# usb_uart.net
KiCad netlist of a schematic drawn in Altium Designer
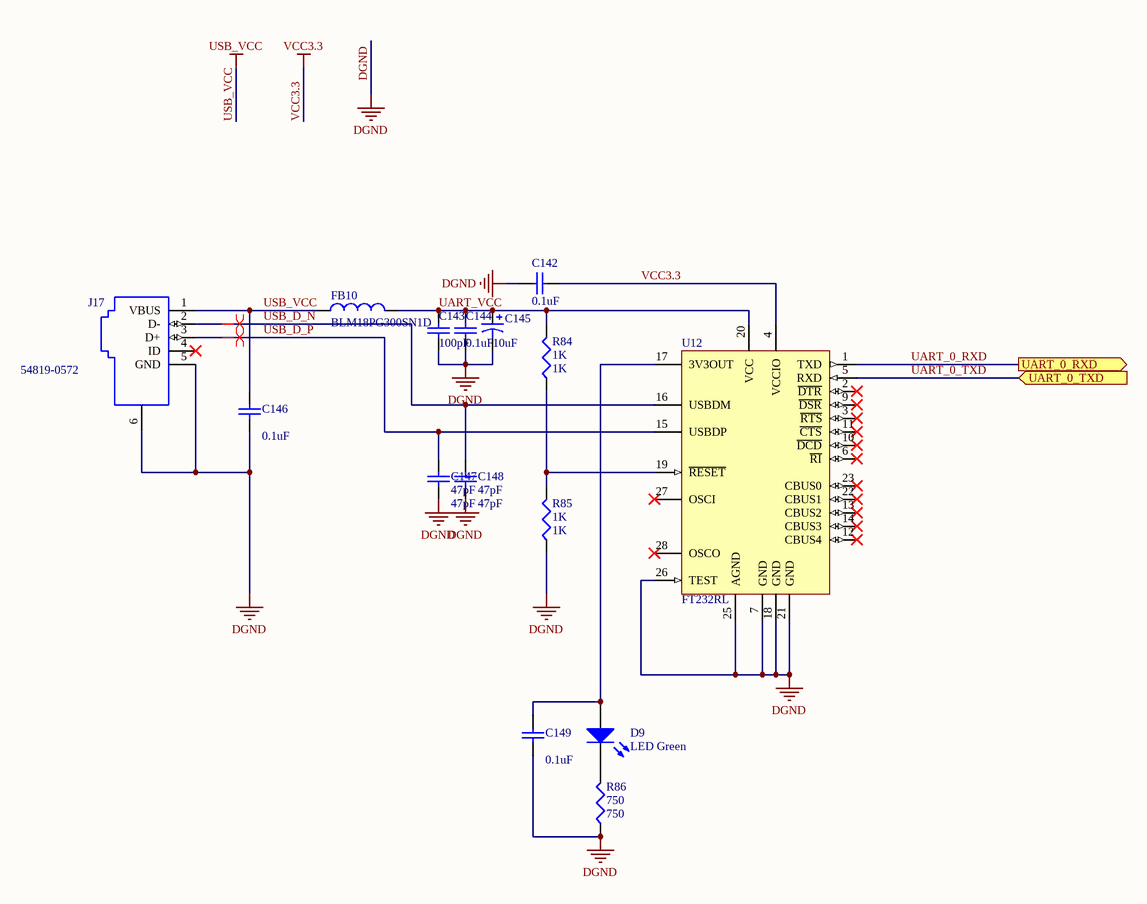
[diagram p0: usb_uart.SchDoc]

(export (version "E")
  (design (tool "Eeschema 10.0.6"))
  (components
    (comp (ref "C142")
      (value "0.1uF")
      (footprint "0402")
      (description "Capacitor (Semiconductor SIM Model)")
      (fields (field (name "PUBLISHER") "Altium Limited"))
      (libsource (lib "Miscellaneous Devices") (part "Cap Semi"))
    )
    (comp (ref "C143")
      (value "100pF")
      (footprint "0402")
      (description "Capacitor (Semiconductor SIM Model)")
      (fields (field (name "PUBLISHER") "Altium Limited"))
      (libsource (lib "Miscellaneous Devices") (part "Cap Semi"))
    )
    (comp (ref "C144")
      (value "0.1uF")
      (footprint "0402")
      (description "Capacitor (Semiconductor SIM Model)")
      (fields (field (name "PUBLISHER") "Altium Limited"))
      (libsource (lib "Miscellaneous Devices") (part "Cap Semi"))
    )
    (comp (ref "C145")
      (value "10uF")
      (footprint "C0805")
      (description "Polarized Capacitor (Surface Mount)")
      (fields (field (name "PUBLISHER") "Altium Limited"))
      (libsource (lib "Miscellaneous Devices") (part "Cap Pol3"))
    )
    (comp (ref "C146")
      (value "0.1uF")
      (footprint "0402")
      (description "Capacitor (Semiconductor SIM Model)")
      (fields (field (name "PUBLISHER") "Altium Limited"))
      (libsource (lib "Miscellaneous Devices") (part "Cap Semi"))
    )
    (comp (ref "C147")
      (value "47pF")
      (footprint "0402")
      (description "Capacitor (Semiconductor SIM Model)")
      (fields (field (name "ALTIUM_VALUE") "47pF") (field (name "PUBLISHER") "Altium Limited"))
      (libsource (lib "Miscellaneous Devices") (part "Cap Semi"))
    )
    (comp (ref "C148")
      (value "47pF")
      (footprint "0402")
      (description "Capacitor (Semiconductor SIM Model)")
      (fields (field (name "ALTIUM_VALUE") "47pF") (field (name "PUBLISHER") "Altium Limited"))
      (libsource (lib "Miscellaneous Devices") (part "Cap Semi"))
    )
    (comp (ref "C149")
      (value "0.1uF")
      (footprint "0402")
      (description "Capacitor (Semiconductor SIM Model)")
      (fields (field (name "PUBLISHER") "Altium Limited"))
      (libsource (lib "Miscellaneous Devices") (part "Cap Semi"))
    )
    (comp (ref "D9")
      (value "LED Green")
      (footprint "1608[0603]")
      (description "Typical RED, GREEN, YELLOW, AMBER GaAs LED")
      (fields (field (name "PUBLISHER") "Altium Limited"))
      (libsource (lib "Miscellaneous Devices") (part "LED2"))
    )
    (comp (ref "FB10")
      (value "BLM18PG300SN1D")
      (footprint "1608[0603]")
      (description "FERRITE CHIP 30 OHM 1000MA 0603")
      (libsource (lib "SDR") (part "Ferrite Bead"))
    )
    (comp (ref "J17")
      (value "54819-0572")
      (footprint "Mini USB")
      (description "CONN RECEPT MINIUSB R/A 5POS SMD")
      (libsource (lib "SDR") (part "Mini USB"))
    )
    (comp (ref "R84")
      (value "1K")
      (footprint "0402")
      (description "Resistor")
      (fields (field (name "ALTIUM_VALUE") "1K") (field (name "PUBLISHER") "Altium Limited"))
      (libsource (lib "Miscellaneous Devices") (part "Res3"))
    )
    (comp (ref "R85")
      (value "1K")
      (footprint "0402")
      (description "Resistor")
      (fields (field (name "ALTIUM_VALUE") "1K") (field (name "PUBLISHER") "Altium Limited"))
      (libsource (lib "Miscellaneous Devices") (part "Res3"))
    )
    (comp (ref "R86")
      (value "750")
      (footprint "0402")
      (description "Resistor")
      (fields (field (name "ALTIUM_VALUE") "750") (field (name "PUBLISHER") "Altium Limited"))
      (libsource (lib "Miscellaneous Devices") (part "Res3"))
    )
    (comp (ref "U12")
      (value "FT232RL")
      (footprint "FTDI Footprints:SSOP65P780X200-28N")
      (description "USB to UART interface in SSOP-28 package")
      (fields
        (field (name "MANUFACTURER") "Future Technology Devices International Ltd. (FTDI)")
        (field (name "DIGIKEYPARTNO") "768-1007-1-ND")
        (field (name "PUBLISHER") "FTDI Ltd.")
      )
      (libsource (lib "FTDI Symbols") (part "FT232RL"))
    )
  )
  (nets
    (net (code "1") (name "/UART_0_RXD") (class "Default")
      (node (ref "U12") (pin "1") (pinfunction "TXD_1") (pintype "output"))
    )
    (net (code "2") (name "/UART_0_TXD") (class "Default")
      (node (ref "U12") (pin "5") (pinfunction "RXD_5") (pintype "input"))
    )
    (net (code "3") (name "/UART_VCC") (class "Default")
      (node (ref "C143") (pin "2") (pinfunction "2_2") (pintype "passive"))
      (node (ref "C144") (pin "2") (pinfunction "2_2") (pintype "passive"))
      (node (ref "C145") (pin "1") (pinfunction "1_1") (pintype "passive"))
      (node (ref "FB10") (pin "2") (pinfunction "2_2") (pintype "passive"))
      (node (ref "R84") (pin "2") (pinfunction "2_2") (pintype "passive"))
      (node (ref "U12") (pin "20") (pinfunction "VCC_20") (pintype "power_in"))
    )
    (net (code "4") (name "/USB_D_N") (class "Default")
      (node (ref "C148") (pin "2") (pinfunction "2_2") (pintype "passive"))
      (node (ref "J17") (pin "2") (pinfunction "D-_2") (pintype "bidirectional"))
      (node (ref "U12") (pin "16") (pinfunction "USBDM_16") (pintype "passive"))
    )
    (net (code "5") (name "/USB_D_P") (class "Default")
      (node (ref "C147") (pin "2") (pinfunction "2_2") (pintype "passive"))
      (node (ref "J17") (pin "3") (pinfunction "D+_3") (pintype "bidirectional"))
      (node (ref "U12") (pin "15") (pinfunction "USBDP_15") (pintype "passive"))
    )
    (net (code "6") (name "DGND") (class "Default")
      (node (ref "C142") (pin "1") (pinfunction "1_1") (pintype "passive"))
      (node (ref "C143") (pin "1") (pinfunction "1_1") (pintype "passive"))
      (node (ref "C144") (pin "1") (pinfunction "1_1") (pintype "passive"))
      (node (ref "C145") (pin "2") (pinfunction "2_2") (pintype "passive"))
      (node (ref "C146") (pin "1") (pinfunction "1_1") (pintype "passive"))
      (node (ref "C147") (pin "1") (pinfunction "1_1") (pintype "passive"))
      (node (ref "C148") (pin "1") (pinfunction "1_1") (pintype "passive"))
      (node (ref "C149") (pin "1") (pinfunction "1_1") (pintype "passive"))
      (node (ref "J17") (pin "5") (pinfunction "GND_5") (pintype "power_in"))
      (node (ref "J17") (pin "6") (pinfunction "SHIELD_6") (pintype "passive"))
      (node (ref "R85") (pin "1") (pinfunction "1_1") (pintype "passive"))
      (node (ref "R86") (pin "1") (pinfunction "1_1") (pintype "passive"))
      (node (ref "U12") (pin "18") (pinfunction "GND_18") (pintype "power_in"))
      (node (ref "U12") (pin "21") (pinfunction "GND_21") (pintype "power_in"))
      (node (ref "U12") (pin "25") (pinfunction "AGND_25") (pintype "power_in"))
      (node (ref "U12") (pin "26") (pinfunction "TEST_26") (pintype "input"))
      (node (ref "U12") (pin "7") (pinfunction "GND_7") (pintype "power_in"))
    )
    (net (code "7") (name "Net-(D9-A)") (class "Default")
      (node (ref "C149") (pin "2") (pinfunction "2_2") (pintype "passive"))
      (node (ref "D9") (pin "1") (pinfunction "A_1") (pintype "passive"))
      (node (ref "U12") (pin "17") (pinfunction "3V3OUT_17") (pintype "power_in"))
    )
    (net (code "8") (name "Net-(D9-K)") (class "Default")
      (node (ref "D9") (pin "2") (pinfunction "K_2") (pintype "passive"))
      (node (ref "R86") (pin "2") (pinfunction "2_2") (pintype "passive"))
    )
    (net (code "9") (name "Net-(U12-~{RESET})") (class "Default")
      (node (ref "R84") (pin "1") (pinfunction "1_1") (pintype "passive"))
      (node (ref "R85") (pin "2") (pinfunction "2_2") (pintype "passive"))
      (node (ref "U12") (pin "19") (pinfunction "~{RESET}_19") (pintype "input"))
    )
    (net (code "10") (name "USB_VCC") (class "Default")
      (node (ref "C146") (pin "2") (pinfunction "2_2") (pintype "passive"))
      (node (ref "FB10") (pin "1") (pinfunction "1_1") (pintype "passive"))
      (node (ref "J17") (pin "1") (pinfunction "VBUS_1") (pintype "power_in"))
    )
    (net (code "11") (name "VCC3.3") (class "Default")
      (node (ref "C142") (pin "2") (pinfunction "2_2") (pintype "passive"))
      (node (ref "U12") (pin "4") (pinfunction "VCCIO_4") (pintype "power_in"))
    )
    (net (code "12") (name "unconnected-(J17-ID-Pad4)") (class "Default")
      (node (ref "J17") (pin "4") (pinfunction "ID_4") (pintype "passive+no_connect"))
    )
    (net (code "13") (name "unconnected-(U12-CBUS0-Pad23)") (class "Default")
      (node (ref "U12") (pin "23") (pinfunction "CBUS0_23") (pintype "bidirectional+no_connect"))
    )
    (net (code "14") (name "unconnected-(U12-CBUS1-Pad22)") (class "Default")
      (node (ref "U12") (pin "22") (pinfunction "CBUS1_22") (pintype "bidirectional+no_connect"))
    )
    (net (code "15") (name "unconnected-(U12-CBUS2-Pad13)") (class "Default")
      (node (ref "U12") (pin "13") (pinfunction "CBUS2_13") (pintype "bidirectional+no_connect"))
    )
    (net (code "16") (name "unconnected-(U12-CBUS3-Pad14)") (class "Default")
      (node (ref "U12") (pin "14") (pinfunction "CBUS3_14") (pintype "bidirectional+no_connect"))
    )
    (net (code "17") (name "unconnected-(U12-CBUS4-Pad12)") (class "Default")
      (node (ref "U12") (pin "12") (pinfunction "CBUS4_12") (pintype "bidirectional+no_connect"))
    )
    (net (code "18") (name "unconnected-(U12-NC-Pad8)") (class "Default")
      (node (ref "U12") (pin "8") (pinfunction "NC_8") (pintype "passive"))
    )
    (net (code "19") (name "unconnected-(U12-NC-Pad24)") (class "Default")
      (node (ref "U12") (pin "24") (pinfunction "NC_24") (pintype "passive"))
    )
    (net (code "20") (name "unconnected-(U12-OSCI-Pad27)") (class "Default")
      (node (ref "U12") (pin "27") (pinfunction "OSCI_27") (pintype "passive+no_connect"))
    )
    (net (code "21") (name "unconnected-(U12-OSCO-Pad28)") (class "Default")
      (node (ref "U12") (pin "28") (pinfunction "OSCO_28") (pintype "passive+no_connect"))
    )
    (net (code "22") (name "unconnected-(U12-~{CTS}-Pad11)") (class "Default")
      (node (ref "U12") (pin "11") (pinfunction "~{CTS}_11") (pintype "bidirectional+no_connect"))
    )
    (net (code "23") (name "unconnected-(U12-~{DCD}-Pad10)") (class "Default")
      (node (ref "U12") (pin "10") (pinfunction "~{DCD}_10") (pintype "bidirectional+no_connect"))
    )
    (net (code "24") (name "unconnected-(U12-~{DSR}-Pad9)") (class "Default")
      (node (ref "U12") (pin "9") (pinfunction "~{DSR}_9") (pintype "bidirectional+no_connect"))
    )
    (net (code "25") (name "unconnected-(U12-~{DTR}-Pad2)") (class "Default")
      (node (ref "U12") (pin "2") (pinfunction "~{DTR}_2") (pintype "bidirectional+no_connect"))
    )
    (net (code "26") (name "unconnected-(U12-~{RI}-Pad6)") (class "Default")
      (node (ref "U12") (pin "6") (pinfunction "~{RI}_6") (pintype "bidirectional+no_connect"))
    )
    (net (code "27") (name "unconnected-(U12-~{RTS}-Pad3)") (class "Default")
      (node (ref "U12") (pin "3") (pinfunction "~{RTS}_3") (pintype "bidirectional+no_connect"))
    )
  )
)
